# Ender_3_control_panel.net
KiCad netlist of a schematic drawn in EasyEDA
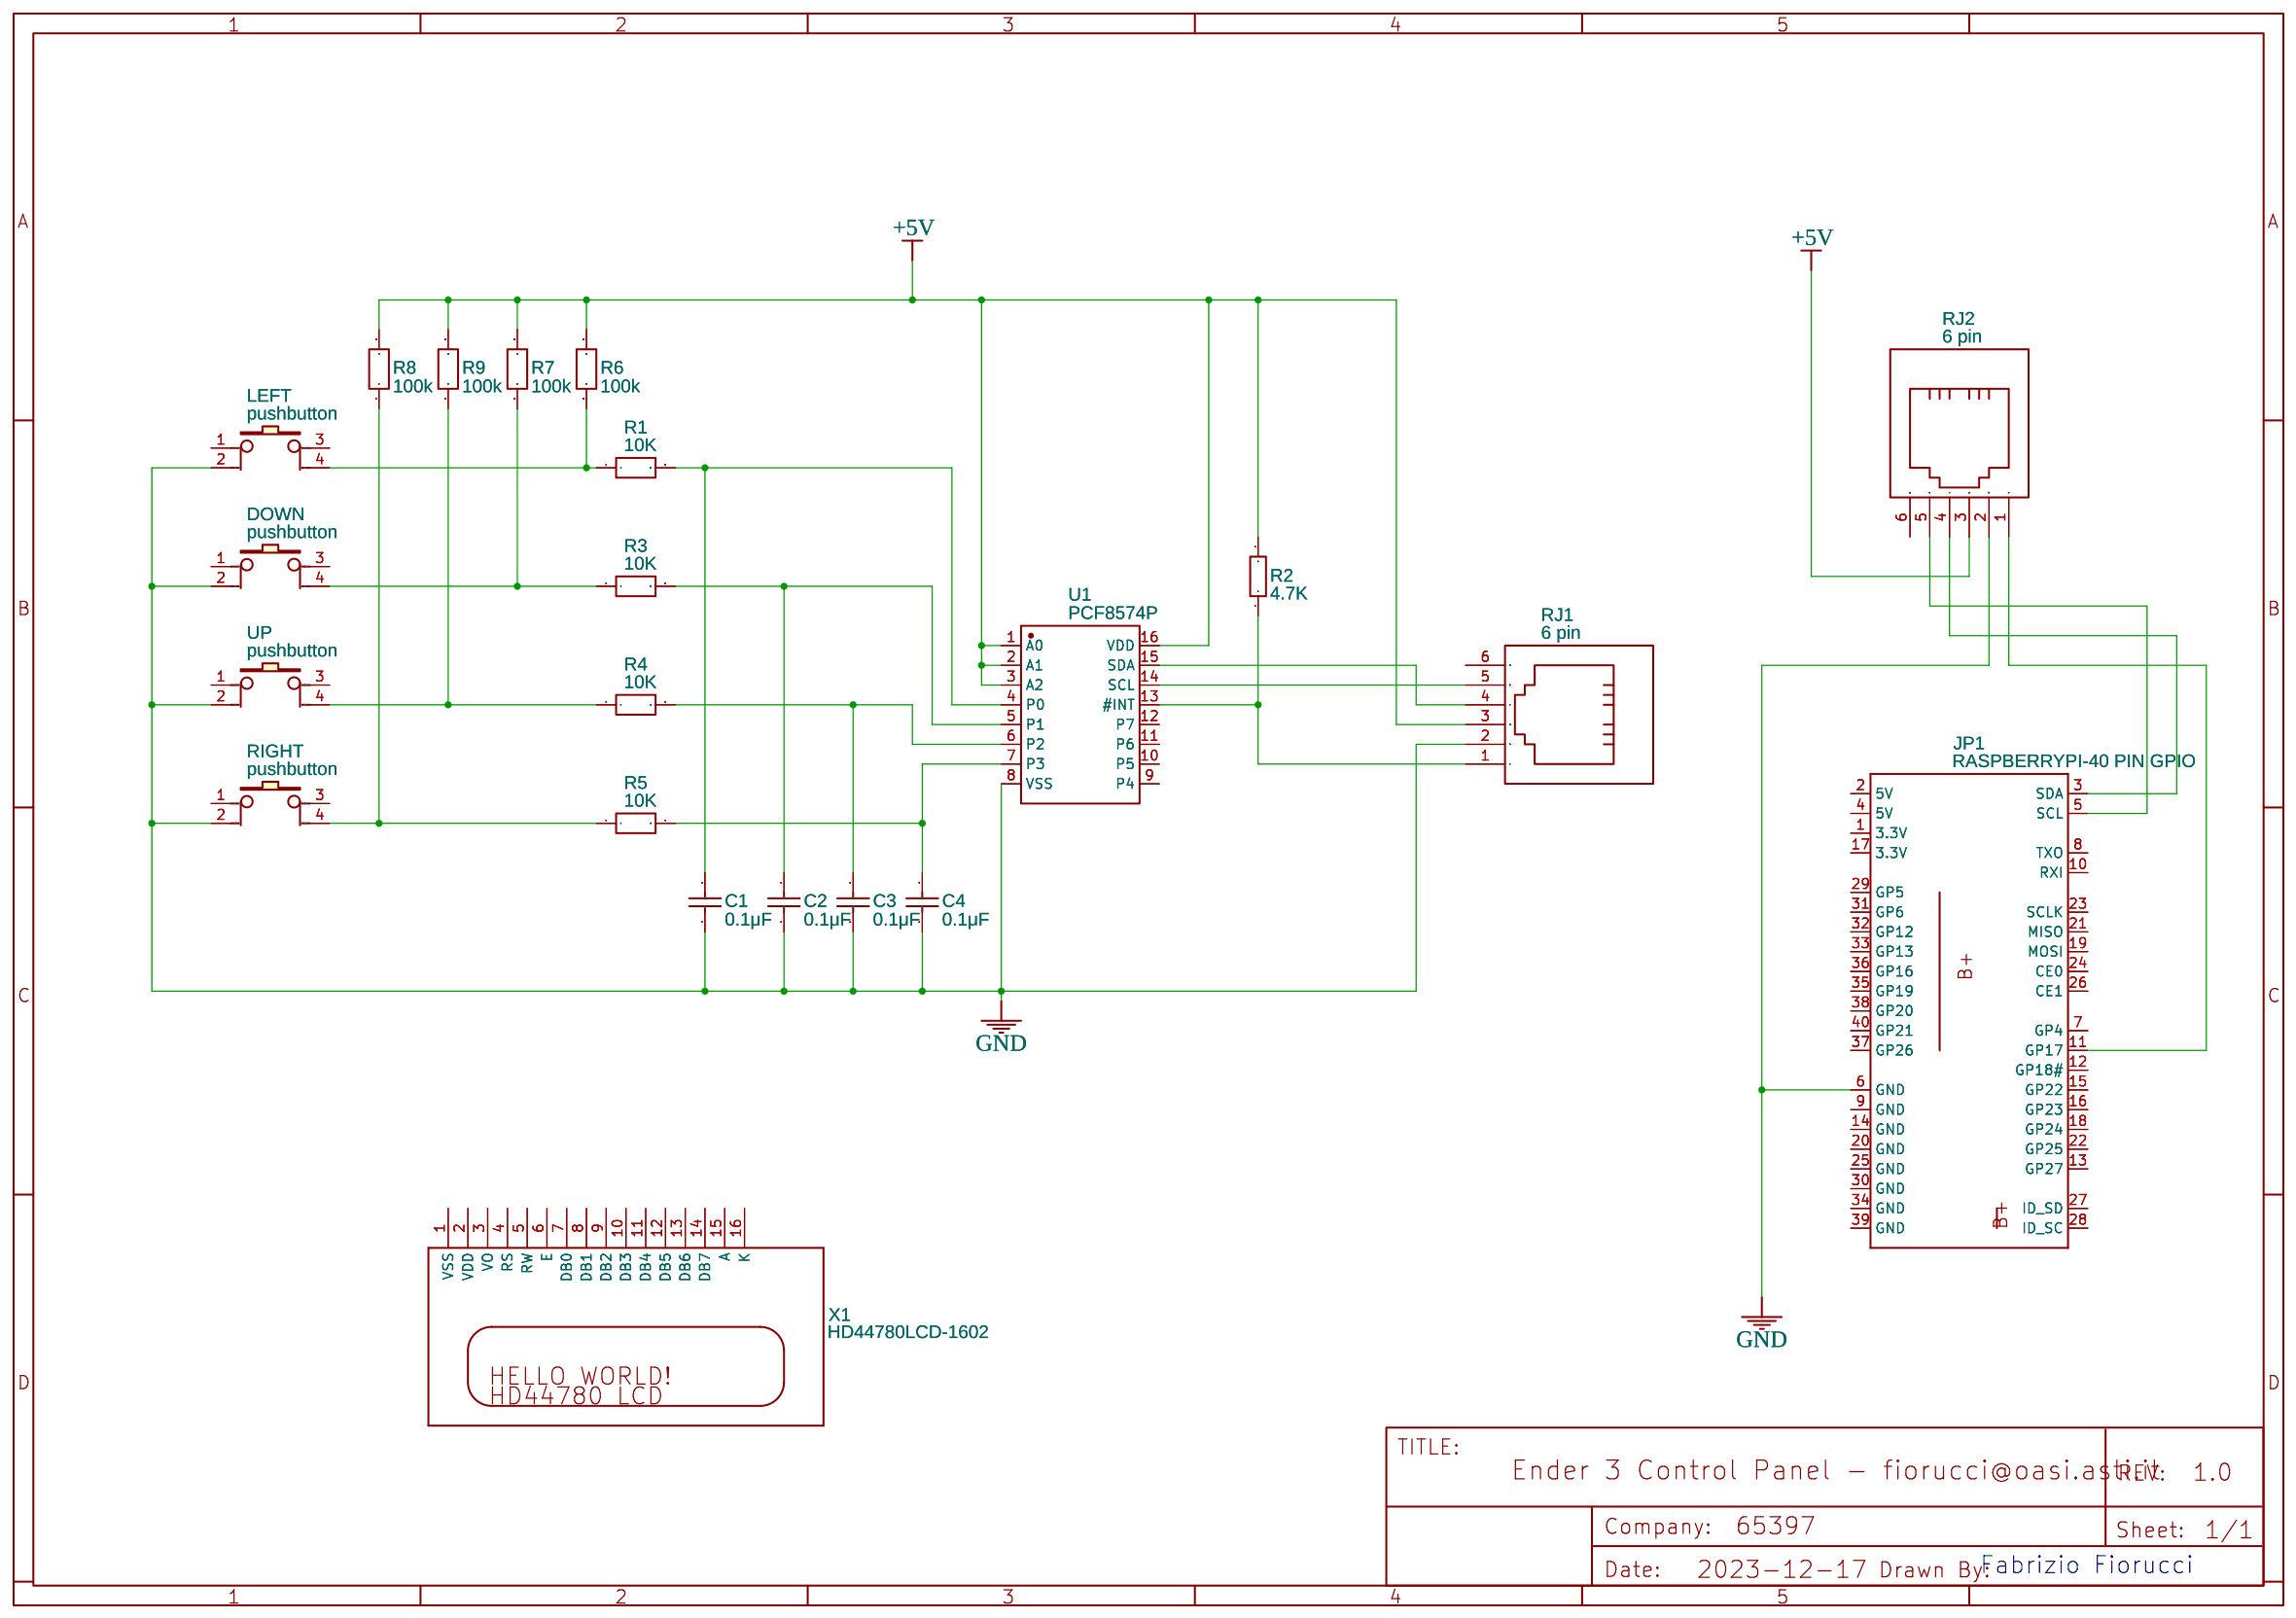
[diagram p0: schematic sheet]

(export (version "E")
  (design (tool "Eeschema 10.0.6"))
  (components
    (comp (ref "C1")
      (value "0.1μF")
      (fields (field (name "Manufacturer Part") "Capacitor15nf100v") (field (name "Manufacturer") "ReliaPro"))
      (libsource (lib "") (part "CAPACITOR15NF100V"))
    )
    (comp (ref "C2")
      (value "0.1μF")
      (fields (field (name "Manufacturer Part") "Capacitor15nf100v") (field (name "Manufacturer") "ReliaPro"))
      (libsource (lib "") (part "CAPACITOR15NF100V"))
    )
    (comp (ref "C3")
      (value "0.1μF")
      (fields (field (name "Manufacturer Part") "Capacitor15nf100v") (field (name "Manufacturer") "ReliaPro"))
      (libsource (lib "") (part "CAPACITOR15NF100V"))
    )
    (comp (ref "C4")
      (value "0.1μF")
      (fields (field (name "Manufacturer Part") "Capacitor15nf100v") (field (name "Manufacturer") "ReliaPro"))
      (libsource (lib "") (part "CAPACITOR15NF100V"))
    )
    (comp (ref "DOWN")
      (value "pushbutton")
      (fields (field (name "Manufacturer Part") "button6*6*8.5") (field (name "Manufacturer") "ReliaPro"))
      (libsource (lib "") (part "button6*6*8.5_2"))
    )
    (comp (ref "JP1") (value "RASPBERRYPI-40 PIN GPIO") (libsource (lib "") (part "RASPBERRYPI-B+-GPIO")))
    (comp (ref "LEFT")
      (value "pushbutton")
      (fields (field (name "Manufacturer Part") "button6*6*8.5") (field (name "Manufacturer") "ReliaPro"))
      (libsource (lib "") (part "button6*6*8.5_1"))
    )
    (comp (ref "R1")
      (value "10K")
      (fields (field (name "Manufacturer Part") "RD 3WS 10K J T/B A1") (field (name "Manufacturer") "TyoHM"))
      (libsource (lib "") (part "RD 3WS 10K J T/B A1"))
    )
    (comp (ref "R2")
      (value "4.7K")
      (fields (field (name "Manufacturer Part") "CFR0W4J0472A50") (field (name "Manufacturer") "UniOhm"))
      (libsource (lib "") (part "CFR0W4J0472A50"))
    )
    (comp (ref "R3")
      (value "10K")
      (fields (field (name "Manufacturer Part") "RD 3WS 10K J T/B A1") (field (name "Manufacturer") "TyoHM"))
      (libsource (lib "") (part "RD 3WS 10K J T/B A1"))
    )
    (comp (ref "R4")
      (value "10K")
      (fields (field (name "Manufacturer Part") "RD 3WS 10K J T/B A1") (field (name "Manufacturer") "TyoHM"))
      (libsource (lib "") (part "RD 3WS 10K J T/B A1"))
    )
    (comp (ref "R5")
      (value "10K")
      (fields (field (name "Manufacturer Part") "RD 3WS 10K J T/B A1") (field (name "Manufacturer") "TyoHM"))
      (libsource (lib "") (part "RD 3WS 10K J T/B A1"))
    )
    (comp (ref "R6")
      (value "100k")
      (fields (field (name "Manufacturer Part") "RD 3WS 10K J T/B A1") (field (name "Manufacturer") "TyoHM"))
      (libsource (lib "") (part "RD 3WS 10K J T/B A1_1"))
    )
    (comp (ref "R7")
      (value "100k")
      (fields (field (name "Manufacturer Part") "RD 3WS 10K J T/B A1") (field (name "Manufacturer") "TyoHM"))
      (libsource (lib "") (part "RD 3WS 10K J T/B A1_1"))
    )
    (comp (ref "R8")
      (value "100k")
      (fields (field (name "Manufacturer Part") "RD 3WS 10K J T/B A1") (field (name "Manufacturer") "TyoHM"))
      (libsource (lib "") (part "RD 3WS 10K J T/B A1_1"))
    )
    (comp (ref "R9")
      (value "100k")
      (fields (field (name "Manufacturer Part") "RD 3WS 10K J T/B A1") (field (name "Manufacturer") "TyoHM"))
      (libsource (lib "") (part "RD 3WS 10K J T/B A1_1"))
    )
    (comp (ref "RIGHT")
      (value "pushbutton")
      (fields (field (name "Manufacturer Part") "button6*6*8.5") (field (name "Manufacturer") "ReliaPro"))
      (libsource (lib "") (part "button6*6*8.5_3"))
    )
    (comp (ref "RJ1")
      (value "6 pin")
      (fields (field (name "Manufacturer Part") "DS1133-S60BPX") (field (name "Manufacturer") "CONNFLY"))
      (libsource (lib "") (part "DS1133-S60BPX_1"))
    )
    (comp (ref "RJ2")
      (value "6 pin")
      (fields (field (name "Manufacturer Part") "DS1133-S60BPX") (field (name "Manufacturer") "CONNFLY"))
      (libsource (lib "") (part "DS1133-S60BPX"))
    )
    (comp (ref "U1")
      (value "PCF8574P")
      (fields (field (name "Manufacturer") "HGSEMI"))
      (libsource (lib "") (part "PCF8574P"))
    )
    (comp (ref "UP")
      (value "pushbutton")
      (fields (field (name "Manufacturer Part") "button6*6*8.5") (field (name "Manufacturer") "ReliaPro"))
      (libsource (lib "") (part "button6*6*8.5"))
    )
    (comp (ref "X1") (value "HD44780LCD-1602") (libsource (lib "") (part "HD44780LCD-1602")))
  )
  (nets
    (net (code "1") (name "+5V") (class "Default")
      (node (ref "R2") (pin "2") (pinfunction "2_2") (pintype "input"))
      (node (ref "R6") (pin "2") (pinfunction "2_2") (pintype "unspecified"))
      (node (ref "R7") (pin "2") (pinfunction "2_2") (pintype "unspecified"))
      (node (ref "R8") (pin "2") (pinfunction "2_2") (pintype "unspecified"))
      (node (ref "R9") (pin "2") (pinfunction "2_2") (pintype "unspecified"))
      (node (ref "RJ1") (pin "3") (pinfunction "3_3") (pintype "unspecified"))
      (node (ref "RJ2") (pin "3") (pinfunction "3_3") (pintype "unspecified"))
      (node (ref "U1") (pin "1") (pinfunction "A0_1") (pintype "unspecified"))
      (node (ref "U1") (pin "16") (pinfunction "VDD_16") (pintype "unspecified"))
      (node (ref "U1") (pin "2") (pinfunction "A1_2") (pintype "unspecified"))
      (node (ref "U1") (pin "3") (pinfunction "A2_3") (pintype "unspecified"))
    )
    (net (code "2") (name "GND") (class "Default")
      (node (ref "C1") (pin "1") (pinfunction "1_1") (pintype "input"))
      (node (ref "C2") (pin "1") (pinfunction "1_1") (pintype "input"))
      (node (ref "C3") (pin "1") (pinfunction "1_1") (pintype "input"))
      (node (ref "C4") (pin "1") (pinfunction "1_1") (pintype "input"))
      (node (ref "DOWN") (pin "2") (pinfunction "2_2") (pintype "input"))
      (node (ref "JP1") (pin "6") (pinfunction "GND_6") (pintype "passive"))
      (node (ref "LEFT") (pin "2") (pinfunction "2_2") (pintype "input"))
      (node (ref "RIGHT") (pin "2") (pinfunction "2_2") (pintype "input"))
      (node (ref "RJ1") (pin "2") (pinfunction "2_2") (pintype "unspecified"))
      (node (ref "RJ2") (pin "2") (pinfunction "2_2") (pintype "unspecified"))
      (node (ref "U1") (pin "8") (pinfunction "VSS_8") (pintype "unspecified"))
      (node (ref "UP") (pin "2") (pinfunction "2_2") (pintype "input"))
    )
    (net (code "3") (name "Net-(DOWN-Pad4)") (class "Default")
      (node (ref "DOWN") (pin "4") (pinfunction "4_4") (pintype "input"))
      (node (ref "R3") (pin "1") (pinfunction "1_1") (pintype "unspecified"))
      (node (ref "R7") (pin "1") (pinfunction "1_1") (pintype "unspecified"))
    )
    (net (code "4") (name "Net-(JP1-GP17)") (class "Default")
      (node (ref "JP1") (pin "11") (pinfunction "GP17_11") (pintype "unspecified"))
      (node (ref "RJ2") (pin "1") (pinfunction "1_1") (pintype "unspecified"))
    )
    (net (code "5") (name "Net-(JP1-SCL)") (class "Default")
      (node (ref "JP1") (pin "5") (pinfunction "SCL_5") (pintype "unspecified"))
      (node (ref "RJ2") (pin "5") (pinfunction "5_5") (pintype "unspecified"))
    )
    (net (code "6") (name "Net-(JP1-SDA)") (class "Default")
      (node (ref "JP1") (pin "3") (pinfunction "SDA_3") (pintype "unspecified"))
      (node (ref "RJ2") (pin "4") (pinfunction "4_4") (pintype "unspecified"))
    )
    (net (code "7") (name "Net-(LEFT-Pad4)") (class "Default")
      (node (ref "LEFT") (pin "4") (pinfunction "4_4") (pintype "input"))
      (node (ref "R1") (pin "1") (pinfunction "1_1") (pintype "unspecified"))
      (node (ref "R6") (pin "1") (pinfunction "1_1") (pintype "unspecified"))
    )
    (net (code "8") (name "Net-(R4-Pad1)") (class "Default")
      (node (ref "R4") (pin "1") (pinfunction "1_1") (pintype "unspecified"))
      (node (ref "R9") (pin "1") (pinfunction "1_1") (pintype "unspecified"))
      (node (ref "UP") (pin "4") (pinfunction "4_4") (pintype "input"))
    )
    (net (code "9") (name "Net-(R5-Pad1)") (class "Default")
      (node (ref "R5") (pin "1") (pinfunction "1_1") (pintype "unspecified"))
      (node (ref "R8") (pin "1") (pinfunction "1_1") (pintype "unspecified"))
      (node (ref "RIGHT") (pin "4") (pinfunction "4_4") (pintype "input"))
    )
    (net (code "10") (name "Net-(U1-#INT)") (class "Default")
      (node (ref "R2") (pin "1") (pinfunction "1_1") (pintype "input"))
      (node (ref "RJ1") (pin "1") (pinfunction "1_1") (pintype "unspecified"))
      (node (ref "U1") (pin "13") (pinfunction "#INT_13") (pintype "unspecified"))
    )
    (net (code "11") (name "Net-(U1-P0)") (class "Default")
      (node (ref "C1") (pin "2") (pinfunction "2_2") (pintype "input"))
      (node (ref "R1") (pin "2") (pinfunction "2_2") (pintype "unspecified"))
      (node (ref "U1") (pin "4") (pinfunction "P0_4") (pintype "unspecified"))
    )
    (net (code "12") (name "Net-(U1-P1)") (class "Default")
      (node (ref "C2") (pin "2") (pinfunction "2_2") (pintype "input"))
      (node (ref "R3") (pin "2") (pinfunction "2_2") (pintype "unspecified"))
      (node (ref "U1") (pin "5") (pinfunction "P1_5") (pintype "unspecified"))
    )
    (net (code "13") (name "Net-(U1-P2)") (class "Default")
      (node (ref "C3") (pin "2") (pinfunction "2_2") (pintype "input"))
      (node (ref "R4") (pin "2") (pinfunction "2_2") (pintype "unspecified"))
      (node (ref "U1") (pin "6") (pinfunction "P2_6") (pintype "unspecified"))
    )
    (net (code "14") (name "Net-(U1-P3)") (class "Default")
      (node (ref "C4") (pin "2") (pinfunction "2_2") (pintype "input"))
      (node (ref "R5") (pin "2") (pinfunction "2_2") (pintype "unspecified"))
      (node (ref "U1") (pin "7") (pinfunction "P3_7") (pintype "unspecified"))
    )
    (net (code "15") (name "Net-(U1-SCL)") (class "Default")
      (node (ref "RJ1") (pin "5") (pinfunction "5_5") (pintype "unspecified"))
      (node (ref "U1") (pin "14") (pinfunction "SCL_14") (pintype "unspecified"))
    )
    (net (code "16") (name "Net-(U1-SDA)") (class "Default")
      (node (ref "RJ1") (pin "4") (pinfunction "4_4") (pintype "unspecified"))
      (node (ref "U1") (pin "15") (pinfunction "SDA_15") (pintype "unspecified"))
    )
    (net (code "17") (name "unconnected-(DOWN-Pad1)") (class "Default")
      (node (ref "DOWN") (pin "1") (pinfunction "1_1") (pintype "input"))
    )
    (net (code "18") (name "unconnected-(DOWN-Pad3)") (class "Default")
      (node (ref "DOWN") (pin "3") (pinfunction "3_3") (pintype "input"))
    )
    (net (code "19") (name "unconnected-(JP1-3.3V-Pad1)") (class "Default")
      (node (ref "JP1") (pin "1") (pinfunction "3.3V_1") (pintype "passive"))
    )
    (net (code "20") (name "unconnected-(JP1-3.3V-Pad17)") (class "Default")
      (node (ref "JP1") (pin "17") (pinfunction "3.3V_17") (pintype "passive"))
    )
    (net (code "21") (name "unconnected-(JP1-5V-Pad2)") (class "Default")
      (node (ref "JP1") (pin "2") (pinfunction "5V_2") (pintype "passive"))
    )
    (net (code "22") (name "unconnected-(JP1-5V-Pad4)") (class "Default")
      (node (ref "JP1") (pin "4") (pinfunction "5V_4") (pintype "passive"))
    )
    (net (code "23") (name "unconnected-(JP1-CE0-Pad24)") (class "Default")
      (node (ref "JP1") (pin "24") (pinfunction "CE0_24") (pintype "output"))
    )
    (net (code "24") (name "unconnected-(JP1-CE1-Pad26)") (class "Default")
      (node (ref "JP1") (pin "26") (pinfunction "CE1_26") (pintype "output"))
    )
    (net (code "25") (name "unconnected-(JP1-GND-Pad9)") (class "Default")
      (node (ref "JP1") (pin "9") (pinfunction "GND_9") (pintype "passive"))
    )
    (net (code "26") (name "unconnected-(JP1-GND-Pad14)") (class "Default")
      (node (ref "JP1") (pin "14") (pinfunction "GND_14") (pintype "passive"))
    )
    (net (code "27") (name "unconnected-(JP1-GND-Pad20)") (class "Default")
      (node (ref "JP1") (pin "20") (pinfunction "GND_20") (pintype "passive"))
    )
    (net (code "28") (name "unconnected-(JP1-GND-Pad25)") (class "Default")
      (node (ref "JP1") (pin "25") (pinfunction "GND_25") (pintype "passive"))
    )
    (net (code "29") (name "unconnected-(JP1-GND-Pad30)") (class "Default")
      (node (ref "JP1") (pin "30") (pinfunction "GND_30") (pintype "passive"))
    )
    (net (code "30") (name "unconnected-(JP1-GND-Pad34)") (class "Default")
      (node (ref "JP1") (pin "34") (pinfunction "GND_34") (pintype "passive"))
    )
    (net (code "31") (name "unconnected-(JP1-GND-Pad39)") (class "Default")
      (node (ref "JP1") (pin "39") (pinfunction "GND_39") (pintype "passive"))
    )
    (net (code "32") (name "unconnected-(JP1-GP4-Pad7)") (class "Default")
      (node (ref "JP1") (pin "7") (pinfunction "GP4_7") (pintype "unspecified"))
    )
    (net (code "33") (name "unconnected-(JP1-GP5-Pad29)") (class "Default")
      (node (ref "JP1") (pin "29") (pinfunction "GP5_29") (pintype "unspecified"))
    )
    (net (code "34") (name "unconnected-(JP1-GP6-Pad31)") (class "Default")
      (node (ref "JP1") (pin "31") (pinfunction "GP6_31") (pintype "unspecified"))
    )
    (net (code "35") (name "unconnected-(JP1-GP12-Pad32)") (class "Default")
      (node (ref "JP1") (pin "32") (pinfunction "GP12_32") (pintype "unspecified"))
    )
    (net (code "36") (name "unconnected-(JP1-GP13-Pad33)") (class "Default")
      (node (ref "JP1") (pin "33") (pinfunction "GP13_33") (pintype "unspecified"))
    )
    (net (code "37") (name "unconnected-(JP1-GP16-Pad36)") (class "Default")
      (node (ref "JP1") (pin "36") (pinfunction "GP16_36") (pintype "unspecified"))
    )
    (net (code "38") (name "unconnected-(JP1-GP18#-Pad12)") (class "Default")
      (node (ref "JP1") (pin "12") (pinfunction "GP18#_12") (pintype "unspecified"))
    )
    (net (code "39") (name "unconnected-(JP1-GP19-Pad35)") (class "Default")
      (node (ref "JP1") (pin "35") (pinfunction "GP19_35") (pintype "unspecified"))
    )
    (net (code "40") (name "unconnected-(JP1-GP20-Pad38)") (class "Default")
      (node (ref "JP1") (pin "38") (pinfunction "GP20_38") (pintype "unspecified"))
    )
    (net (code "41") (name "unconnected-(JP1-GP21-Pad40)") (class "Default")
      (node (ref "JP1") (pin "40") (pinfunction "GP21_40") (pintype "unspecified"))
    )
    (net (code "42") (name "unconnected-(JP1-GP22-Pad15)") (class "Default")
      (node (ref "JP1") (pin "15") (pinfunction "GP22_15") (pintype "unspecified"))
    )
    (net (code "43") (name "unconnected-(JP1-GP23-Pad16)") (class "Default")
      (node (ref "JP1") (pin "16") (pinfunction "GP23_16") (pintype "unspecified"))
    )
    (net (code "44") (name "unconnected-(JP1-GP24-Pad18)") (class "Default")
      (node (ref "JP1") (pin "18") (pinfunction "GP24_18") (pintype "unspecified"))
    )
    (net (code "45") (name "unconnected-(JP1-GP25-Pad22)") (class "Default")
      (node (ref "JP1") (pin "22") (pinfunction "GP25_22") (pintype "unspecified"))
    )
    (net (code "46") (name "unconnected-(JP1-GP26-Pad37)") (class "Default")
      (node (ref "JP1") (pin "37") (pinfunction "GP26_37") (pintype "unspecified"))
    )
    (net (code "47") (name "unconnected-(JP1-GP27-Pad13)") (class "Default")
      (node (ref "JP1") (pin "13") (pinfunction "GP27_13") (pintype "unspecified"))
    )
    (net (code "48") (name "unconnected-(JP1-ID_SC-Pad28)") (class "Default")
      (node (ref "JP1") (pin "28") (pinfunction "ID_SC_28") (pintype "unspecified"))
    )
    (net (code "49") (name "unconnected-(JP1-ID_SD-Pad27)") (class "Default")
      (node (ref "JP1") (pin "27") (pinfunction "ID_SD_27") (pintype "unspecified"))
    )
    (net (code "50") (name "unconnected-(JP1-MISO-Pad21)") (class "Default")
      (node (ref "JP1") (pin "21") (pinfunction "MISO_21") (pintype "input"))
    )
    (net (code "51") (name "unconnected-(JP1-MOSI-Pad19)") (class "Default")
      (node (ref "JP1") (pin "19") (pinfunction "MOSI_19") (pintype "output"))
    )
    (net (code "52") (name "unconnected-(JP1-RXI-Pad10)") (class "Default")
      (node (ref "JP1") (pin "10") (pinfunction "RXI_10") (pintype "input"))
    )
    (net (code "53") (name "unconnected-(JP1-SCLK-Pad23)") (class "Default")
      (node (ref "JP1") (pin "23") (pinfunction "SCLK_23") (pintype "output"))
    )
    (net (code "54") (name "unconnected-(JP1-TXO-Pad8)") (class "Default")
      (node (ref "JP1") (pin "8") (pinfunction "TXO_8") (pintype "output"))
    )
    (net (code "55") (name "unconnected-(LEFT-Pad1)") (class "Default")
      (node (ref "LEFT") (pin "1") (pinfunction "1_1") (pintype "input"))
    )
    (net (code "56") (name "unconnected-(LEFT-Pad3)") (class "Default")
      (node (ref "LEFT") (pin "3") (pinfunction "3_3") (pintype "input"))
    )
    (net (code "57") (name "unconnected-(RIGHT-Pad1)") (class "Default")
      (node (ref "RIGHT") (pin "1") (pinfunction "1_1") (pintype "input"))
    )
    (net (code "58") (name "unconnected-(RIGHT-Pad3)") (class "Default")
      (node (ref "RIGHT") (pin "3") (pinfunction "3_3") (pintype "input"))
    )
    (net (code "59") (name "unconnected-(RJ1-Pad6)") (class "Default")
      (node (ref "RJ1") (pin "6") (pinfunction "6_6") (pintype "unspecified"))
    )
    (net (code "60") (name "unconnected-(RJ2-Pad6)") (class "Default")
      (node (ref "RJ2") (pin "6") (pinfunction "6_6") (pintype "unspecified"))
    )
    (net (code "61") (name "unconnected-(U1-P4-Pad9)") (class "Default")
      (node (ref "U1") (pin "9") (pinfunction "P4_9") (pintype "unspecified"))
    )
    (net (code "62") (name "unconnected-(U1-P5-Pad10)") (class "Default")
      (node (ref "U1") (pin "10") (pinfunction "P5_10") (pintype "unspecified"))
    )
    (net (code "63") (name "unconnected-(U1-P6-Pad11)") (class "Default")
      (node (ref "U1") (pin "11") (pinfunction "P6_11") (pintype "unspecified"))
    )
    (net (code "64") (name "unconnected-(U1-P7-Pad12)") (class "Default")
      (node (ref "U1") (pin "12") (pinfunction "P7_12") (pintype "unspecified"))
    )
    (net (code "65") (name "unconnected-(UP-Pad1)") (class "Default")
      (node (ref "UP") (pin "1") (pinfunction "1_1") (pintype "input"))
    )
    (net (code "66") (name "unconnected-(UP-Pad3)") (class "Default")
      (node (ref "UP") (pin "3") (pinfunction "3_3") (pintype "input"))
    )
    (net (code "67") (name "unconnected-(X1-A-Pad15)") (class "Default")
      (node (ref "X1") (pin "15") (pinfunction "A_15") (pintype "input"))
    )
    (net (code "68") (name "unconnected-(X1-DB0-Pad7)") (class "Default")
      (node (ref "X1") (pin "7") (pinfunction "DB0_7") (pintype "unspecified"))
    )
    (net (code "69") (name "unconnected-(X1-DB1-Pad8)") (class "Default")
      (node (ref "X1") (pin "8") (pinfunction "DB1_8") (pintype "unspecified"))
    )
    (net (code "70") (name "unconnected-(X1-DB2-Pad9)") (class "Default")
      (node (ref "X1") (pin "9") (pinfunction "DB2_9") (pintype "unspecified"))
    )
    (net (code "71") (name "unconnected-(X1-DB3-Pad10)") (class "Default")
      (node (ref "X1") (pin "10") (pinfunction "DB3_10") (pintype "unspecified"))
    )
    (net (code "72") (name "unconnected-(X1-DB4-Pad11)") (class "Default")
      (node (ref "X1") (pin "11") (pinfunction "DB4_11") (pintype "unspecified"))
    )
    (net (code "73") (name "unconnected-(X1-DB5-Pad12)") (class "Default")
      (node (ref "X1") (pin "12") (pinfunction "DB5_12") (pintype "unspecified"))
    )
    (net (code "74") (name "unconnected-(X1-DB6-Pad13)") (class "Default")
      (node (ref "X1") (pin "13") (pinfunction "DB6_13") (pintype "unspecified"))
    )
    (net (code "75") (name "unconnected-(X1-DB7-Pad14)") (class "Default")
      (node (ref "X1") (pin "14") (pinfunction "DB7_14") (pintype "unspecified"))
    )
    (net (code "76") (name "unconnected-(X1-E-Pad6)") (class "Default")
      (node (ref "X1") (pin "6") (pinfunction "E_6") (pintype "input"))
    )
    (net (code "77") (name "unconnected-(X1-K-Pad16)") (class "Default")
      (node (ref "X1") (pin "16") (pinfunction "K_16") (pintype "input"))
    )
    (net (code "78") (name "unconnected-(X1-RS-Pad4)") (class "Default")
      (node (ref "X1") (pin "4") (pinfunction "RS_4") (pintype "input"))
    )
    (net (code "79") (name "unconnected-(X1-RW-Pad5)") (class "Default")
      (node (ref "X1") (pin "5") (pinfunction "RW_5") (pintype "input"))
    )
    (net (code "80") (name "unconnected-(X1-VDD-Pad2)") (class "Default")
      (node (ref "X1") (pin "2") (pinfunction "VDD_2") (pintype "unspecified"))
    )
    (net (code "81") (name "unconnected-(X1-VO-Pad3)") (class "Default")
      (node (ref "X1") (pin "3") (pinfunction "VO_3") (pintype "input"))
    )
    (net (code "82") (name "unconnected-(X1-VSS-Pad1)") (class "Default")
      (node (ref "X1") (pin "1") (pinfunction "VSS_1") (pintype "unspecified"))
    )
  )
)
